# Transmitter-Bug-BC547.net
KiCad netlist of a schematic drawn in EAGLE
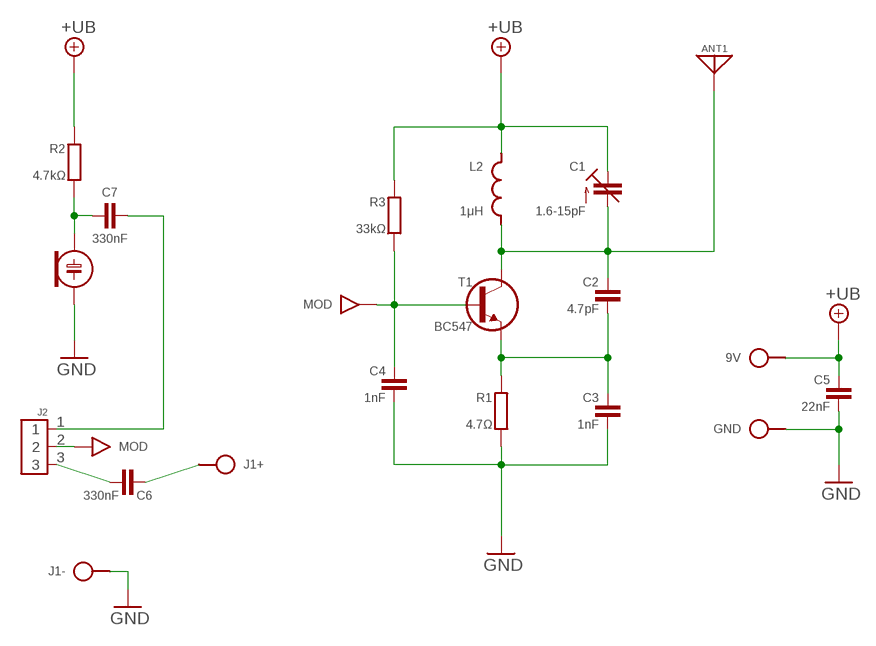
[diagram p0: schematic, sheet 1]

(export (version "E")
  (design (tool "Eeschema 10.0.6"))
  (components
    (comp (ref "9V")
      (value "SPAD")
      (footprint "eagle-import:SPAD")
      (libsource (lib "eagle-import") (part "SPAD"))
    )
    (comp (ref "ANT1")
      (value "ANT")
      (footprint "eagle-import:SPAD")
      (libsource (lib "eagle-import") (part "ANT"))
    )
    (comp (ref "C1")
      (value "1.6-15pF")
      (footprint "eagle-import:TRIM-2222-808")
      (libsource (lib "eagle-import") (part "C-TR-PH201272222-808-2PINB"))
    )
    (comp (ref "C2")
      (value "4.7pF")
      (footprint "eagle-import:C025-015X024")
      (libsource (lib "eagle-import") (part "C025-015X024"))
    )
    (comp (ref "C3")
      (value "1nF")
      (footprint "eagle-import:C025-015X024")
      (libsource (lib "eagle-import") (part "C025-015X024"))
    )
    (comp (ref "C4")
      (value "1nF")
      (footprint "eagle-import:C050-020X036_V")
      (libsource (lib "eagle-import") (part "C050-020X036/V"))
    )
    (comp (ref "C5")
      (value "22nF")
      (footprint "eagle-import:C050-020X036_V")
      (libsource (lib "eagle-import") (part "C050-020X036/V"))
    )
    (comp (ref "C6")
      (value "330nF")
      (footprint "eagle-import:C050-020X044")
      (libsource (lib "eagle-import") (part "C-H050-020X044"))
    )
    (comp (ref "C7")
      (value "330nF")
      (footprint "eagle-import:C050-020X044")
      (libsource (lib "eagle-import") (part "C050-020X044"))
    )
    (comp (ref "ECM")
      (value "ECM-4")
      (footprint "eagle-import:ECM-4")
      (libsource (lib "eagle-import") (part "ECM-4"))
    )
    (comp (ref "GND")
      (value "SPAD")
      (footprint "eagle-import:SPAD")
      (libsource (lib "eagle-import") (part "SPAD"))
    )
    (comp (ref "J1")
      (value "SPAD+--+")
      (footprint "eagle-import:SPAD-+")
      (libsource (lib "eagle-import") (part "SPAD+--+"))
    )
    (comp (ref "J2")
      (value "CONN-3P-3P")
      (footprint "eagle-import:CONN-3P")
      (libsource (lib "eagle-import") (part "CONN-3P-3P"))
    )
    (comp (ref "L2")
      (value "1μH")
      (footprint "eagle-import:L-04_7V-X")
      (libsource (lib "eagle-import") (part "L-SHORT04/7V-X"))
    )
    (comp (ref "R1")
      (value "4.7Ω")
      (footprint "eagle-import:0204_2V")
      (libsource (lib "eagle-import") (part "R0204/2V"))
    )
    (comp (ref "R2")
      (value "4.7kΩ")
      (footprint "eagle-import:0202_7-V")
      (libsource (lib "eagle-import") (part "R0202/7-V"))
    )
    (comp (ref "R3")
      (value "33kΩ")
      (footprint "eagle-import:0202_7-V")
      (libsource (lib "eagle-import") (part "R0202/7-V"))
    )
    (comp (ref "T1")
      (value "BC547")
      (footprint "eagle-import:TO92-CBE")
      (libsource (lib "eagle-import") (part "BC547CBE"))
    )
  )
  (nets
    (net (code "1") (name "+UB") (class "Default")
      (node (ref "9V") (pin "1") (pinfunction "P$1_1") (pintype "passive"))
      (node (ref "C1") (pin "3") (pinfunction "E_3") (pintype "passive"))
      (node (ref "C5") (pin "1") (pinfunction "1_1") (pintype "passive"))
      (node (ref "L2") (pin "2") (pinfunction "2_2") (pintype "passive"))
      (node (ref "R2") (pin "1") (pinfunction "1_1") (pintype "passive"))
      (node (ref "R3") (pin "1") (pinfunction "1_1") (pintype "passive"))
    )
    (net (code "2") (name "GND") (class "Default")
      (node (ref "C3") (pin "2") (pinfunction "2_2") (pintype "passive"))
      (node (ref "C4") (pin "2") (pinfunction "2_2") (pintype "passive"))
      (node (ref "C5") (pin "2") (pinfunction "2_2") (pintype "passive"))
      (node (ref "ECM") (pin "2") (pinfunction "-_2") (pintype "passive"))
      (node (ref "GND") (pin "1") (pinfunction "P$1_1") (pintype "passive"))
      (node (ref "J1") (pin "1") (pinfunction "P$1_1") (pintype "passive"))
      (node (ref "R1") (pin "2") (pinfunction "2_2") (pintype "passive"))
    )
    (net (code "3") (name "MOD") (class "Default")
      (node (ref "C4") (pin "1") (pinfunction "1_1") (pintype "passive"))
      (node (ref "J2") (pin "2") (pinfunction "2_2") (pintype "bidirectional"))
      (node (ref "R3") (pin "2") (pinfunction "2_2") (pintype "passive"))
      (node (ref "T1") (pin "B") (pinfunction "B_B") (pintype "passive"))
    )
    (net (code "4") (name "Net-(C1-A)") (class "Default")
      (node (ref "ANT1") (pin "1") (pinfunction "1_1") (pintype "output"))
      (node (ref "C1") (pin "2") (pinfunction "A_2") (pintype "passive"))
      (node (ref "C2") (pin "1") (pinfunction "1_1") (pintype "passive"))
      (node (ref "L2") (pin "1") (pinfunction "1_1") (pintype "passive"))
      (node (ref "T1") (pin "C") (pinfunction "C_C") (pintype "passive"))
    )
    (net (code "5") (name "Net-(C2-Pad2)") (class "Default")
      (node (ref "C2") (pin "2") (pinfunction "2_2") (pintype "passive"))
      (node (ref "C3") (pin "1") (pinfunction "1_1") (pintype "passive"))
      (node (ref "R1") (pin "1") (pinfunction "1_1") (pintype "passive"))
      (node (ref "T1") (pin "E") (pinfunction "E_E") (pintype "passive"))
    )
    (net (code "6") (name "Net-(C6-Pad2)") (class "Default")
      (node (ref "C6") (pin "2") (pinfunction "2_2") (pintype "passive"))
      (node (ref "J2") (pin "3") (pinfunction "3_3") (pintype "bidirectional"))
    )
    (net (code "7") (name "Net-(C7-Pad2)") (class "Default")
      (node (ref "C7") (pin "2") (pinfunction "2_2") (pintype "passive"))
      (node (ref "J2") (pin "1") (pinfunction "1_1") (pintype "bidirectional"))
    )
    (net (code "8") (name "Net-(ECM-+)") (class "Default")
      (node (ref "C7") (pin "1") (pinfunction "1_1") (pintype "passive"))
      (node (ref "ECM") (pin "1") (pinfunction "+_1") (pintype "passive"))
      (node (ref "R2") (pin "2") (pinfunction "2_2") (pintype "passive"))
    )
    (net (code "9") (name "Net-(J1A-P$1)") (class "Default")
      (node (ref "C6") (pin "1") (pinfunction "1_1") (pintype "passive"))
      (node (ref "J1") (pin "2") (pinfunction "P$1_2") (pintype "passive"))
    )
  )
)
